# esquem_tico_CPLD.net
KiCad netlist of a schematic drawn in EAGLE
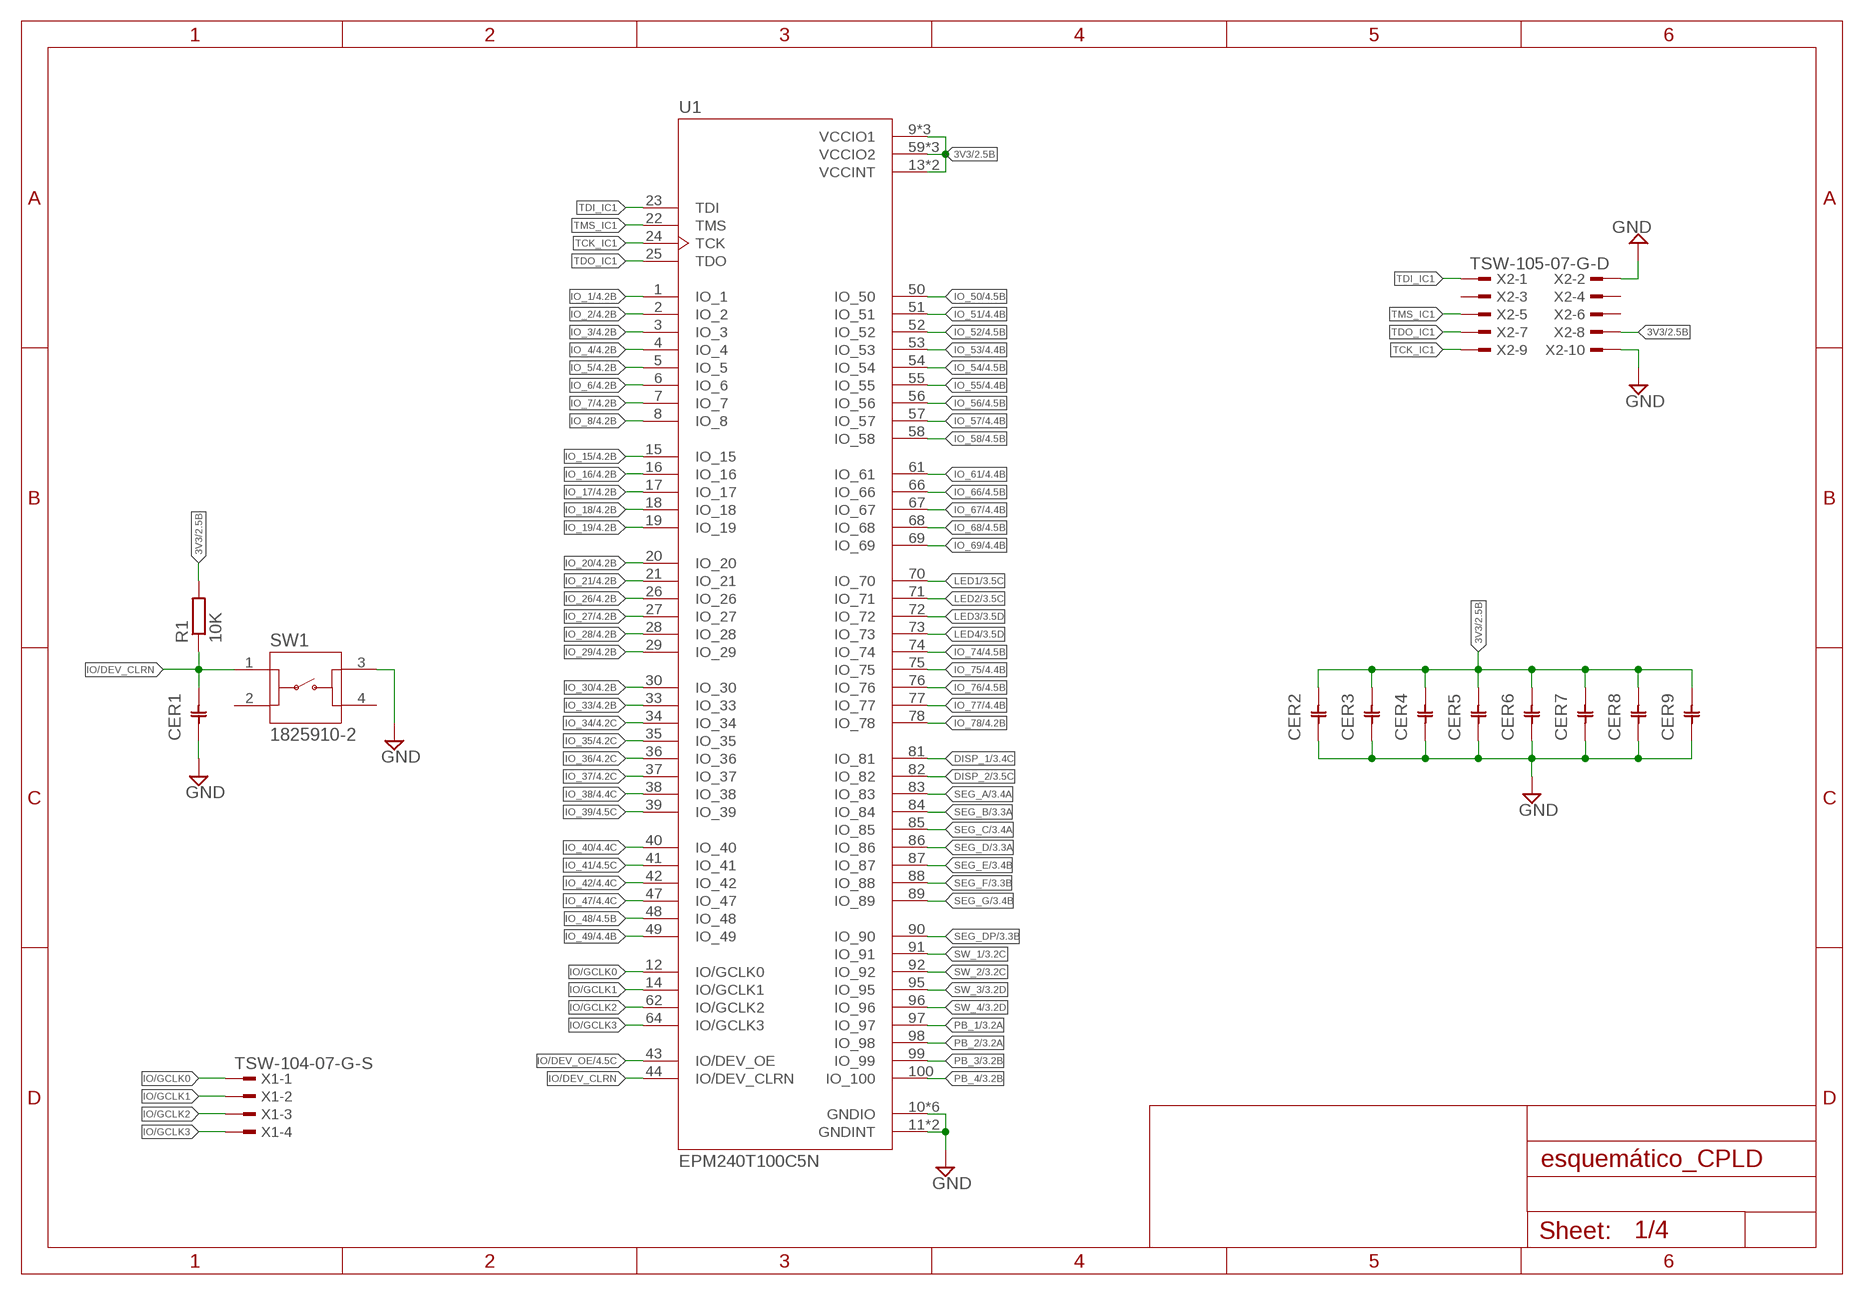
[diagram p0: schematic, sheet 1]
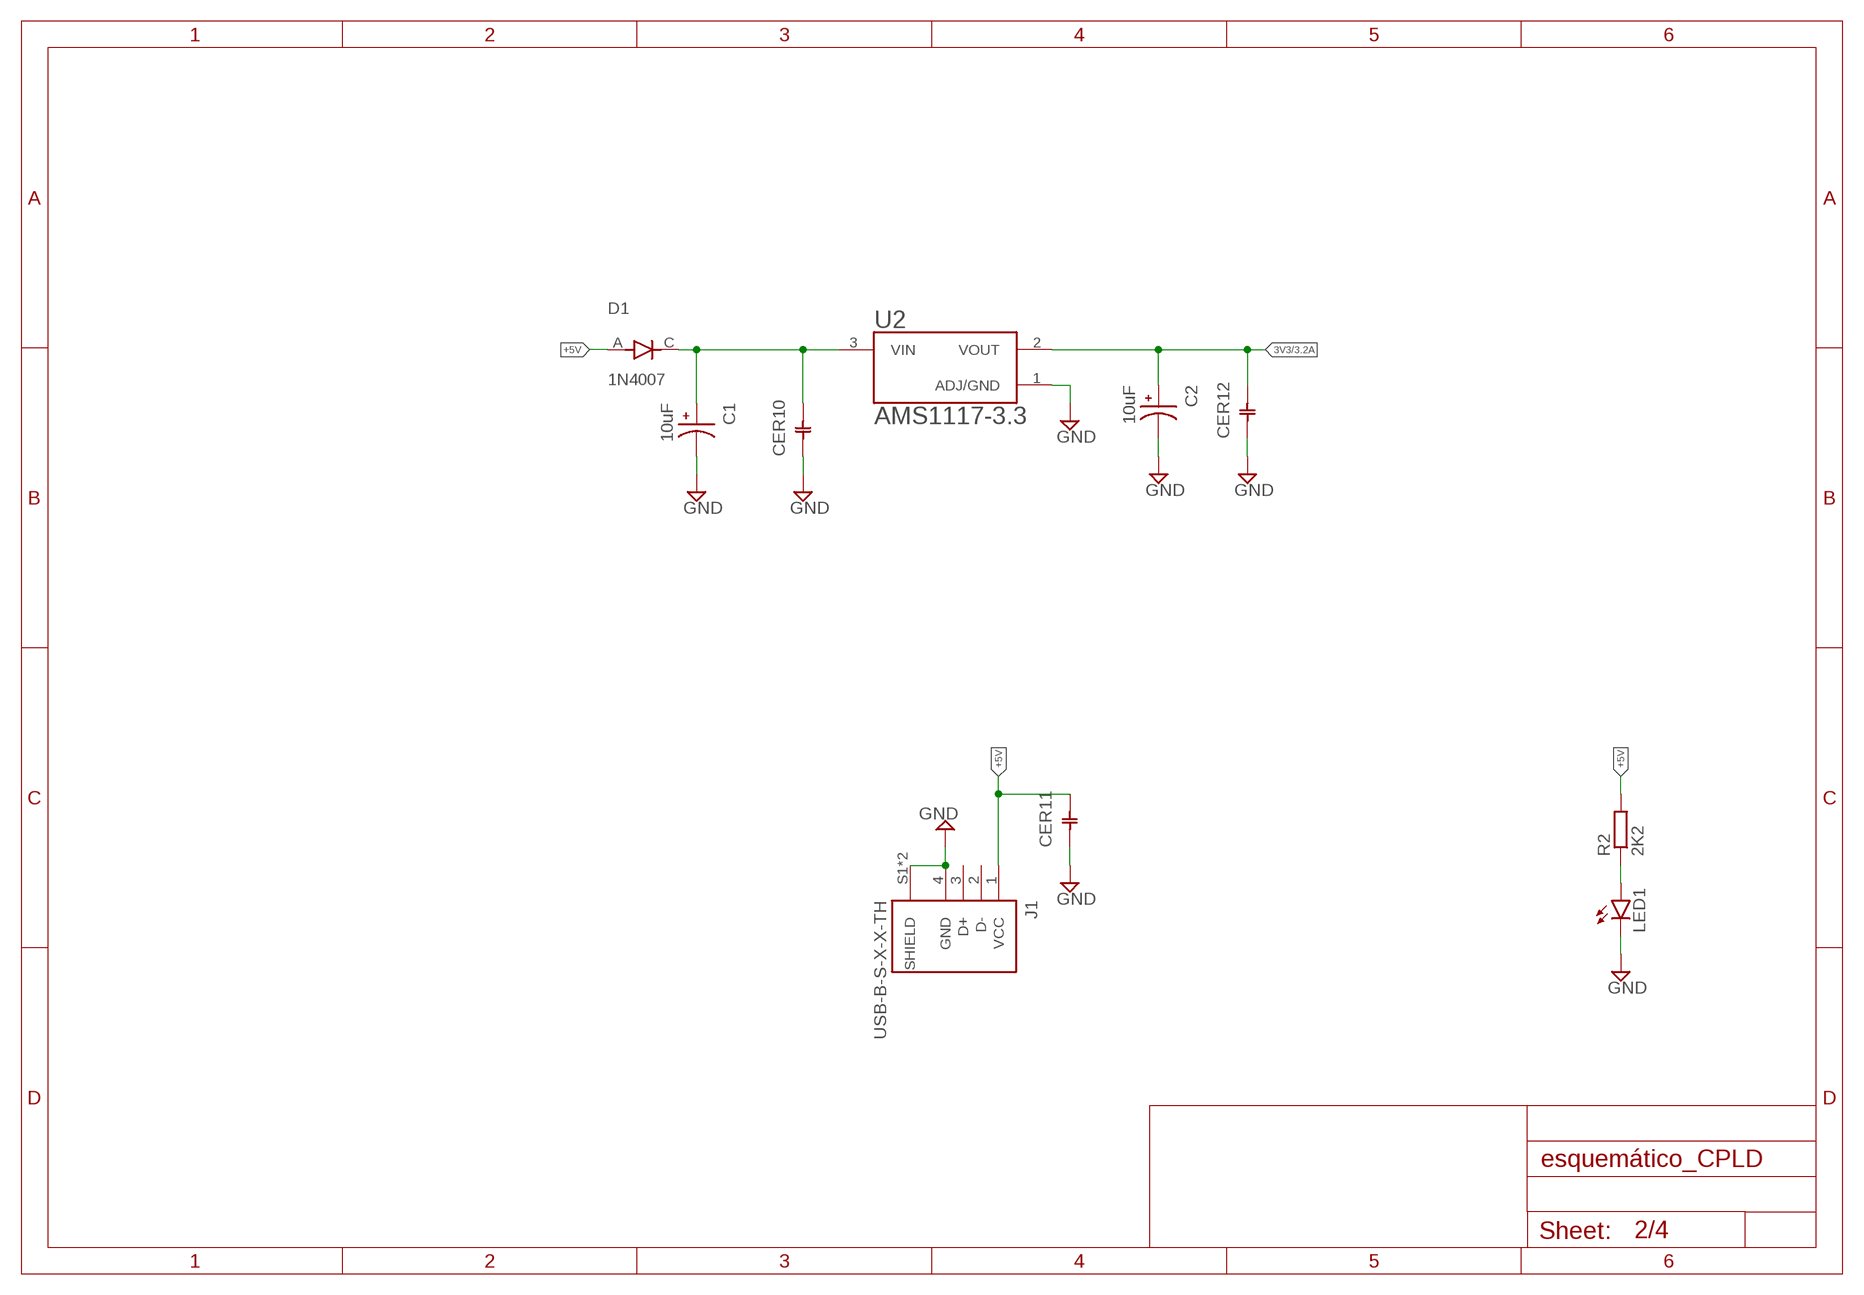
[diagram p1: schematic, sheet 2]
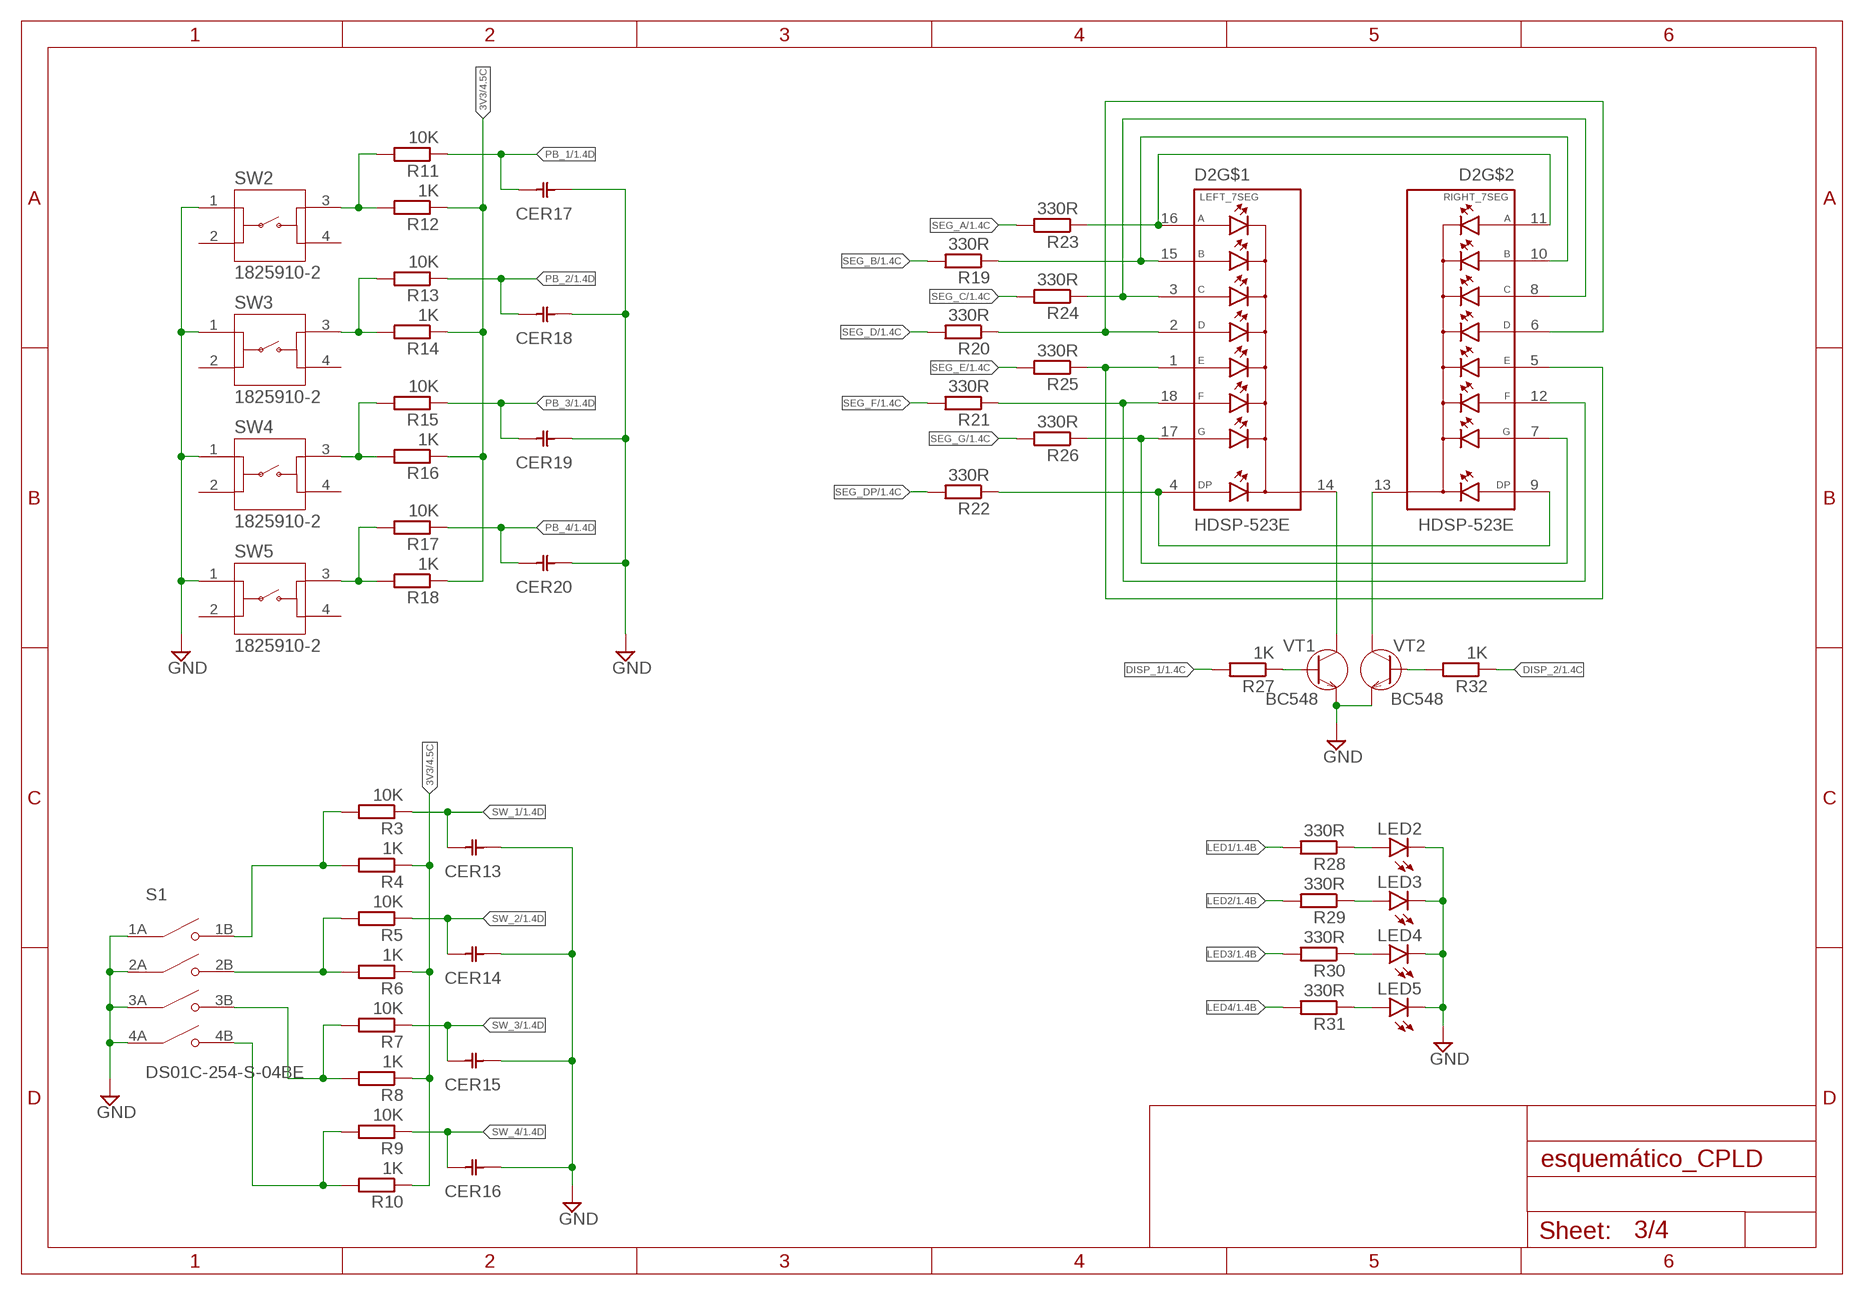
[diagram p2: schematic, sheet 3]
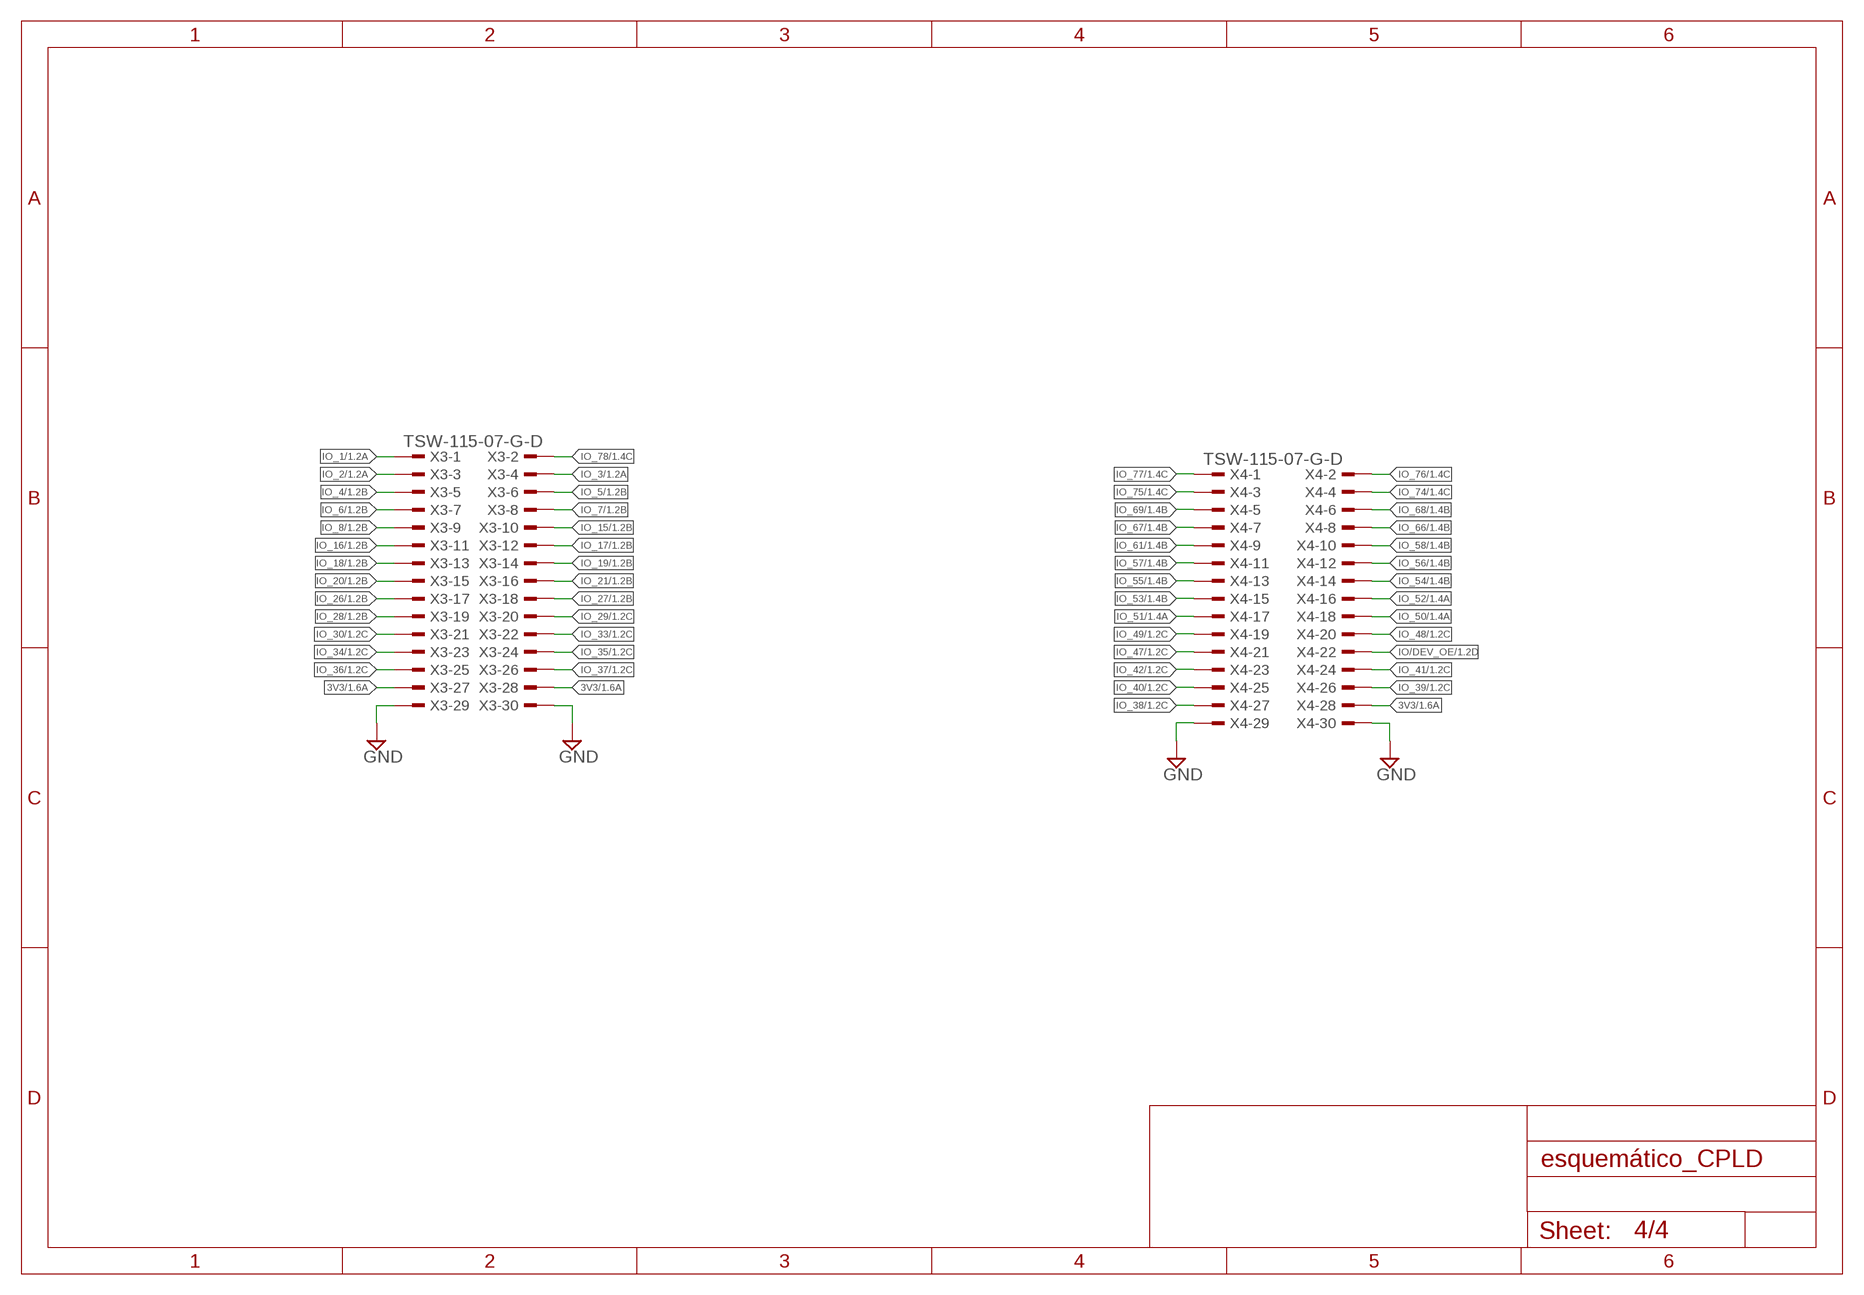
[diagram p3: schematic, sheet 4]

(export (version "E")
  (design (tool "Eeschema 10.0.6"))
  (components
    (comp (ref "CER1")
      (value "100nF")
      (footprint "eagle-import:CERACAPA")
      (libsource (lib "eagle-import") (part "-CERACAP"))
    )
    (comp (ref "CER2")
      (value "100nF")
      (footprint "eagle-import:CERACAPA")
      (libsource (lib "eagle-import") (part "-CERACAP"))
    )
    (comp (ref "CER3")
      (value "100nF")
      (footprint "eagle-import:CERACAPA")
      (libsource (lib "eagle-import") (part "-CERACAP"))
    )
    (comp (ref "CER4")
      (value "100nF")
      (footprint "eagle-import:CERACAPA")
      (libsource (lib "eagle-import") (part "-CERACAP"))
    )
    (comp (ref "CER5")
      (value "100nF")
      (footprint "eagle-import:CERACAPA")
      (libsource (lib "eagle-import") (part "-CERACAP"))
    )
    (comp (ref "CER6")
      (value "100nF")
      (footprint "eagle-import:CERACAPA")
      (libsource (lib "eagle-import") (part "-CERACAP"))
    )
    (comp (ref "CER7")
      (value "100nF")
      (footprint "eagle-import:CERACAPA")
      (libsource (lib "eagle-import") (part "-CERACAP"))
    )
    (comp (ref "CER8")
      (value "100nF")
      (footprint "eagle-import:CERACAPA")
      (libsource (lib "eagle-import") (part "-CERACAP"))
    )
    (comp (ref "CER9")
      (value "100nF")
      (footprint "eagle-import:CERACAPA")
      (libsource (lib "eagle-import") (part "-CERACAP"))
    )
    (comp (ref "R1")
      (value "10K")
      (footprint "eagle-import:0204_7")
      (libsource (lib "eagle-import") (part "R-EU_0204/7"))
    )
    (comp (ref "SW1")
      (value "1825910-2")
      (footprint "eagle-import:TE_1825910-2")
      (fields (field (name "MF") "TE Connectivity"))
      (libsource (lib "eagle-import") (part "1825910-2"))
    )
    (comp (ref "U1")
      (value "EPM240T100C5N")
      (footprint "eagle-import:QFP50P1600X1600X120-100N")
      (fields (field (name "MF") "Intel"))
      (libsource (lib "eagle-import") (part "EPM240T100C5N"))
    )
    (comp (ref "X1")
      (value "TSW-104-07-G-S")
      (footprint "eagle-import:TSW-104-XX-G-S")
      (fields (field (name "MF") "Samtec Inc."))
      (libsource (lib "eagle-import") (part "TSW-104--G-S07"))
    )
    (comp (ref "X2")
      (value "TSW-105-07-G-D")
      (footprint "eagle-import:TSW-105-XX-G-D")
      (fields (field (name "MF") "Samtec Inc."))
      (libsource (lib "eagle-import") (part "TSW-105--G-D07"))
    )
    (comp (ref "C1")
      (value "10uF")
      (footprint "eagle-import:CAPPRD150W45D400H700")
      (fields (field (name "MF") "Panasonic") (field (name "MP") "EEAGA1E100"))
      (libsource (lib "eagle-import") (part "EEAGA1E100"))
    )
    (comp (ref "C2")
      (value "10uF")
      (footprint "eagle-import:CAPPRD150W45D400H700")
      (fields (field (name "MF") "Panasonic") (field (name "MP") "EEAGA1E100"))
      (libsource (lib "eagle-import") (part "EEAGA1E100"))
    )
    (comp (ref "CER10")
      (value "100nF")
      (footprint "eagle-import:CERACAPA")
      (libsource (lib "eagle-import") (part "-CERACAP"))
    )
    (comp (ref "CER11")
      (value "100nF")
      (footprint "eagle-import:CERACAPA")
      (libsource (lib "eagle-import") (part "-CERACAP"))
    )
    (comp (ref "CER12")
      (value "100nF")
      (footprint "eagle-import:CERACAPA")
      (libsource (lib "eagle-import") (part "-CERACAP"))
    )
    (comp (ref "D1")
      (value "1N4007")
      (footprint "eagle-import:DIOAD1060W80L520D270")
      (fields (field (name "MF") "Multicomp") (field (name "MP") "1N4007."))
      (libsource (lib "eagle-import") (part "1N4007"))
    )
    (comp (ref "J1")
      (value "USB-B-S-X-X-TH")
      (footprint "eagle-import:SAMTEC_USB-B-S-X-X-TH")
      (fields (field (name "MF") "Samtec") (field (name "MP") "USB-B-S-F-B-TH-TR"))
      (libsource (lib "eagle-import") (part "USB-B-S-X-X-TH"))
    )
    (comp (ref "LED1")
      (value "LED5MM")
      (footprint "eagle-import:LED5MM")
      (libsource (lib "eagle-import") (part "LED5MM"))
    )
    (comp (ref "R2")
      (value "2K2")
      (footprint "eagle-import:0204_7")
      (libsource (lib "eagle-import") (part "R-EU_0204/7"))
    )
    (comp (ref "U2")
      (value "AMS1117-3.3")
      (footprint "eagle-import:SOT229P700X180-4N")
      (fields (field (name "MF") "Advanced Monolithic Systems"))
      (libsource (lib "eagle-import") (part "AMS1117-3.3"))
    )
    (comp (ref "X3")
      (value "TSW-115-07-G-D")
      (footprint "eagle-import:TSW-115-XX-G-D")
      (fields (field (name "MF") "Samtec Inc."))
      (libsource (lib "eagle-import") (part "TSW-115--G-D07"))
    )
    (comp (ref "X4")
      (value "TSW-115-07-G-D")
      (footprint "eagle-import:TSW-115-XX-G-D")
      (fields (field (name "MF") "Samtec Inc."))
      (libsource (lib "eagle-import") (part "TSW-115--G-D07"))
    )
    (comp (ref "CER13")
      (value "100nF")
      (footprint "eagle-import:CERACAPA")
      (libsource (lib "eagle-import") (part "-CERACAP"))
    )
    (comp (ref "CER14")
      (value "100nF")
      (footprint "eagle-import:CERACAPA")
      (libsource (lib "eagle-import") (part "-CERACAP"))
    )
    (comp (ref "CER15")
      (value "100nF")
      (footprint "eagle-import:CERACAPA")
      (libsource (lib "eagle-import") (part "-CERACAP"))
    )
    (comp (ref "CER16")
      (value "100nF")
      (footprint "eagle-import:CERACAPA")
      (libsource (lib "eagle-import") (part "-CERACAP"))
    )
    (comp (ref "CER17")
      (value "100nF")
      (footprint "eagle-import:CERACAPA")
      (libsource (lib "eagle-import") (part "-CERACAP"))
    )
    (comp (ref "CER18")
      (value "100nF")
      (footprint "eagle-import:CERACAPA")
      (libsource (lib "eagle-import") (part "-CERACAP"))
    )
    (comp (ref "CER19")
      (value "100nF")
      (footprint "eagle-import:CERACAPA")
      (libsource (lib "eagle-import") (part "-CERACAP"))
    )
    (comp (ref "CER20")
      (value "100nF")
      (footprint "eagle-import:CERACAPA")
      (libsource (lib "eagle-import") (part "-CERACAP"))
    )
    (comp (ref "D2")
      (value "HDSP-523E")
      (footprint "eagle-import:LED_HDSP-523E")
      (fields (field (name "MF") "Broadcom"))
      (libsource (lib "eagle-import") (part "HDSP-523E"))
    )
    (comp (ref "LED2")
      (value "LED5MM")
      (footprint "eagle-import:LED5MM")
      (libsource (lib "eagle-import") (part "LED5MM"))
    )
    (comp (ref "LED3")
      (value "LED5MM")
      (footprint "eagle-import:LED5MM")
      (libsource (lib "eagle-import") (part "LED5MM"))
    )
    (comp (ref "LED4")
      (value "LED5MM")
      (footprint "eagle-import:LED5MM")
      (libsource (lib "eagle-import") (part "LED5MM"))
    )
    (comp (ref "LED5")
      (value "LED5MM")
      (footprint "eagle-import:LED5MM")
      (libsource (lib "eagle-import") (part "LED5MM"))
    )
    (comp (ref "R3")
      (value "10K")
      (footprint "eagle-import:0204_7")
      (libsource (lib "eagle-import") (part "R-EU_0204/7"))
    )
    (comp (ref "R4")
      (value "1K")
      (footprint "eagle-import:0204_7")
      (libsource (lib "eagle-import") (part "R-EU_0204/7"))
    )
    (comp (ref "R5")
      (value "10K")
      (footprint "eagle-import:0204_7")
      (libsource (lib "eagle-import") (part "R-EU_0204/7"))
    )
    (comp (ref "R6")
      (value "1K")
      (footprint "eagle-import:0204_7")
      (libsource (lib "eagle-import") (part "R-EU_0204/7"))
    )
    (comp (ref "R7")
      (value "10K")
      (footprint "eagle-import:0204_7")
      (libsource (lib "eagle-import") (part "R-EU_0204/7"))
    )
    (comp (ref "R8")
      (value "1K")
      (footprint "eagle-import:0204_7")
      (libsource (lib "eagle-import") (part "R-EU_0204/7"))
    )
    (comp (ref "R9")
      (value "10K")
      (footprint "eagle-import:0204_7")
      (libsource (lib "eagle-import") (part "R-EU_0204/7"))
    )
    (comp (ref "R10")
      (value "1K")
      (footprint "eagle-import:0204_7")
      (libsource (lib "eagle-import") (part "R-EU_0204/7"))
    )
    (comp (ref "R11")
      (value "10K")
      (footprint "eagle-import:0204_7")
      (libsource (lib "eagle-import") (part "R-EU_0204/7"))
    )
    (comp (ref "R12")
      (value "1K")
      (footprint "eagle-import:0204_7")
      (libsource (lib "eagle-import") (part "R-EU_0204/7"))
    )
    (comp (ref "R13")
      (value "10K")
      (footprint "eagle-import:0204_7")
      (libsource (lib "eagle-import") (part "R-EU_0204/7"))
    )
    (comp (ref "R14")
      (value "1K")
      (footprint "eagle-import:0204_7")
      (libsource (lib "eagle-import") (part "R-EU_0204/7"))
    )
    (comp (ref "R15")
      (value "10K")
      (footprint "eagle-import:0204_7")
      (libsource (lib "eagle-import") (part "R-EU_0204/7"))
    )
    (comp (ref "R16")
      (value "1K")
      (footprint "eagle-import:0204_7")
      (libsource (lib "eagle-import") (part "R-EU_0204/7"))
    )
    (comp (ref "R17")
      (value "10K")
      (footprint "eagle-import:0204_7")
      (libsource (lib "eagle-import") (part "R-EU_0204/7"))
    )
    (comp (ref "R18")
      (value "1K")
      (footprint "eagle-import:0204_7")
      (libsource (lib "eagle-import") (part "R-EU_0204/7"))
    )
    (comp (ref "R19")
      (value "330R")
      (footprint "eagle-import:0204_7")
      (libsource (lib "eagle-import") (part "R-EU_0204/7"))
    )
    (comp (ref "R20")
      (value "330R")
      (footprint "eagle-import:0204_7")
      (libsource (lib "eagle-import") (part "R-EU_0204/7"))
    )
    (comp (ref "R21")
      (value "330R")
      (footprint "eagle-import:0204_7")
      (libsource (lib "eagle-import") (part "R-EU_0204/7"))
    )
    (comp (ref "R22")
      (value "330R")
      (footprint "eagle-import:0204_7")
      (libsource (lib "eagle-import") (part "R-EU_0204/7"))
    )
    (comp (ref "R23")
      (value "330R")
      (footprint "eagle-import:0204_7")
      (libsource (lib "eagle-import") (part "R-EU_0204/7"))
    )
    (comp (ref "R24")
      (value "330R")
      (footprint "eagle-import:0204_7")
      (libsource (lib "eagle-import") (part "R-EU_0204/7"))
    )
    (comp (ref "R25")
      (value "330R")
      (footprint "eagle-import:0204_7")
      (libsource (lib "eagle-import") (part "R-EU_0204/7"))
    )
    (comp (ref "R26")
      (value "330R")
      (footprint "eagle-import:0204_7")
      (libsource (lib "eagle-import") (part "R-EU_0204/7"))
    )
    (comp (ref "R27")
      (value "1K")
      (footprint "eagle-import:0204_7")
      (libsource (lib "eagle-import") (part "R-EU_0204/7"))
    )
    (comp (ref "R28")
      (value "330R")
      (footprint "eagle-import:0204_7")
      (libsource (lib "eagle-import") (part "R-EU_0204/7"))
    )
    (comp (ref "R29")
      (value "330R")
      (footprint "eagle-import:0204_7")
      (libsource (lib "eagle-import") (part "R-EU_0204/7"))
    )
    (comp (ref "R30")
      (value "330R")
      (footprint "eagle-import:0204_7")
      (libsource (lib "eagle-import") (part "R-EU_0204/7"))
    )
    (comp (ref "R31")
      (value "330R")
      (footprint "eagle-import:0204_7")
      (libsource (lib "eagle-import") (part "R-EU_0204/7"))
    )
    (comp (ref "R32")
      (value "1K")
      (footprint "eagle-import:0204_7")
      (libsource (lib "eagle-import") (part "R-EU_0204/7"))
    )
    (comp (ref "S1")
      (value "DS01C-254-S-04BE")
      (footprint "eagle-import:SW_DS01C-254-S-04BE")
      (fields (field (name "MF") "CUI Devices"))
      (libsource (lib "eagle-import") (part "DS01C-254-S-04BE"))
    )
    (comp (ref "SW2")
      (value "1825910-2")
      (footprint "eagle-import:TE_1825910-2")
      (fields (field (name "MF") "TE Connectivity"))
      (libsource (lib "eagle-import") (part "1825910-2"))
    )
    (comp (ref "SW3")
      (value "1825910-2")
      (footprint "eagle-import:TE_1825910-2")
      (fields (field (name "MF") "TE Connectivity"))
      (libsource (lib "eagle-import") (part "1825910-2"))
    )
    (comp (ref "SW4")
      (value "1825910-2")
      (footprint "eagle-import:TE_1825910-2")
      (fields (field (name "MF") "TE Connectivity"))
      (libsource (lib "eagle-import") (part "1825910-2"))
    )
    (comp (ref "SW5")
      (value "1825910-2")
      (footprint "eagle-import:TE_1825910-2")
      (fields (field (name "MF") "TE Connectivity"))
      (libsource (lib "eagle-import") (part "1825910-2"))
    )
    (comp (ref "VT1")
      (value "BC548")
      (footprint "eagle-import:TO92")
      (fields (field (name "MF") "ON"))
      (libsource (lib "eagle-import") (part "BC548"))
    )
    (comp (ref "VT2")
      (value "BC548")
      (footprint "eagle-import:TO92")
      (fields (field (name "MF") "ON"))
      (libsource (lib "eagle-import") (part "BC548"))
    )
  )
  (nets
    (net (code "1") (name "+5V") (class "Default")
      (node (ref "CER11") (pin "P$2") (pinfunction "P$2_P$2") (pintype "passive"))
      (node (ref "D1") (pin "A") (pinfunction "A_A") (pintype "passive"))
      (node (ref "J1") (pin "1") (pinfunction "VCC_1") (pintype "power_in"))
      (node (ref "R2") (pin "2") (pinfunction "2_2") (pintype "passive"))
    )
    (net (code "2") (name "3V3") (class "Default")
      (node (ref "C2") (pin "P") (pinfunction "P_P") (pintype "passive"))
      (node (ref "CER12") (pin "P$2") (pinfunction "P$2_P$2") (pintype "passive"))
      (node (ref "CER2") (pin "P$2") (pinfunction "P$2_P$2") (pintype "passive"))
      (node (ref "CER3") (pin "P$2") (pinfunction "P$2_P$2") (pintype "passive"))
      (node (ref "CER4") (pin "P$2") (pinfunction "P$2_P$2") (pintype "passive"))
      (node (ref "CER5") (pin "P$2") (pinfunction "P$2_P$2") (pintype "passive"))
      (node (ref "CER6") (pin "P$2") (pinfunction "P$2_P$2") (pintype "passive"))
      (node (ref "CER7") (pin "P$2") (pinfunction "P$2_P$2") (pintype "passive"))
      (node (ref "CER8") (pin "P$2") (pinfunction "P$2_P$2") (pintype "passive"))
      (node (ref "CER9") (pin "P$2") (pinfunction "P$2_P$2") (pintype "passive"))
      (node (ref "R1") (pin "2") (pinfunction "2_2") (pintype "passive"))
      (node (ref "R10") (pin "1") (pinfunction "1_1") (pintype "passive"))
      (node (ref "R12") (pin "1") (pinfunction "1_1") (pintype "passive"))
      (node (ref "R14") (pin "1") (pinfunction "1_1") (pintype "passive"))
      (node (ref "R16") (pin "1") (pinfunction "1_1") (pintype "passive"))
      (node (ref "R18") (pin "1") (pinfunction "1_1") (pintype "passive"))
      (node (ref "R4") (pin "1") (pinfunction "1_1") (pintype "passive"))
      (node (ref "R6") (pin "1") (pinfunction "1_1") (pintype "passive"))
      (node (ref "R8") (pin "1") (pinfunction "1_1") (pintype "passive"))
      (node (ref "U1") (pin "13") (pinfunction "VCCINT_13") (pintype "power_in"))
      (node (ref "U1") (pin "31") (pinfunction "VCCIO1_31") (pintype "power_in"))
      (node (ref "U1") (pin "45") (pinfunction "VCCIO1_45") (pintype "power_in"))
      (node (ref "U1") (pin "59") (pinfunction "VCCIO2_59") (pintype "power_in"))
      (node (ref "U1") (pin "63") (pinfunction "VCCINT_63") (pintype "power_in"))
      (node (ref "U1") (pin "80") (pinfunction "VCCIO2_80") (pintype "power_in"))
      (node (ref "U1") (pin "9") (pinfunction "VCCIO1_9") (pintype "power_in"))
      (node (ref "U1") (pin "94") (pinfunction "VCCIO2_94") (pintype "power_in"))
      (node (ref "U2") (pin "2") (pinfunction "VOUT_2") (pintype "output"))
      (node (ref "X2") (pin "8") (pinfunction "1_8") (pintype "passive"))
      (node (ref "X3") (pin "27") (pinfunction "1_27") (pintype "passive"))
      (node (ref "X3") (pin "28") (pinfunction "1_28") (pintype "passive"))
      (node (ref "X4") (pin "28") (pinfunction "1_28") (pintype "passive"))
    )
    (net (code "3") (name "DISP_1") (class "Default")
      (node (ref "R27") (pin "2") (pinfunction "2_2") (pintype "passive"))
      (node (ref "U1") (pin "81") (pinfunction "IO_81_81") (pintype "bidirectional"))
    )
    (net (code "4") (name "DISP_2") (class "Default")
      (node (ref "R32") (pin "1") (pinfunction "1_1") (pintype "passive"))
      (node (ref "U1") (pin "82") (pinfunction "IO_82_82") (pintype "bidirectional"))
    )
    (net (code "5") (name "GND") (class "Default")
      (node (ref "C1") (pin "N") (pinfunction "N_N") (pintype "passive"))
      (node (ref "C2") (pin "N") (pinfunction "N_N") (pintype "passive"))
      (node (ref "CER1") (pin "P$1") (pinfunction "P$1_P$1") (pintype "passive"))
      (node (ref "CER10") (pin "P$1") (pinfunction "P$1_P$1") (pintype "passive"))
      (node (ref "CER11") (pin "P$1") (pinfunction "P$1_P$1") (pintype "passive"))
      (node (ref "CER12") (pin "P$1") (pinfunction "P$1_P$1") (pintype "passive"))
      (node (ref "CER13") (pin "P$1") (pinfunction "P$1_P$1") (pintype "passive"))
      (node (ref "CER14") (pin "P$1") (pinfunction "P$1_P$1") (pintype "passive"))
      (node (ref "CER15") (pin "P$1") (pinfunction "P$1_P$1") (pintype "passive"))
      (node (ref "CER16") (pin "P$1") (pinfunction "P$1_P$1") (pintype "passive"))
      (node (ref "CER17") (pin "P$1") (pinfunction "P$1_P$1") (pintype "passive"))
      (node (ref "CER18") (pin "P$1") (pinfunction "P$1_P$1") (pintype "passive"))
      (node (ref "CER19") (pin "P$1") (pinfunction "P$1_P$1") (pintype "passive"))
      (node (ref "CER2") (pin "P$1") (pinfunction "P$1_P$1") (pintype "passive"))
      (node (ref "CER20") (pin "P$1") (pinfunction "P$1_P$1") (pintype "passive"))
      (node (ref "CER3") (pin "P$1") (pinfunction "P$1_P$1") (pintype "passive"))
      (node (ref "CER4") (pin "P$1") (pinfunction "P$1_P$1") (pintype "passive"))
      (node (ref "CER5") (pin "P$1") (pinfunction "P$1_P$1") (pintype "passive"))
      (node (ref "CER6") (pin "P$1") (pinfunction "P$1_P$1") (pintype "passive"))
      (node (ref "CER7") (pin "P$1") (pinfunction "P$1_P$1") (pintype "passive"))
      (node (ref "CER8") (pin "P$1") (pinfunction "P$1_P$1") (pintype "passive"))
      (node (ref "CER9") (pin "P$1") (pinfunction "P$1_P$1") (pintype "passive"))
      (node (ref "J1") (pin "4") (pinfunction "GND_4") (pintype "power_in"))
      (node (ref "J1") (pin "S1") (pinfunction "SHIELD_S1") (pintype "passive"))
      (node (ref "J1") (pin "S2") (pinfunction "SHIELD_S2") (pintype "passive"))
      (node (ref "LED1") (pin "K") (pinfunction "C_K") (pintype "passive"))
      (node (ref "LED2") (pin "K") (pinfunction "C_K") (pintype "passive"))
      (node (ref "LED3") (pin "K") (pinfunction "C_K") (pintype "passive"))
      (node (ref "LED4") (pin "K") (pinfunction "C_K") (pintype "passive"))
      (node (ref "LED5") (pin "K") (pinfunction "C_K") (pintype "passive"))
      (node (ref "S1") (pin "1A") (pinfunction "COM1_1A") (pintype "passive"))
      (node (ref "S1") (pin "2A") (pinfunction "COM2_2A") (pintype "passive"))
      (node (ref "S1") (pin "3A") (pinfunction "COM3_3A") (pintype "passive"))
      (node (ref "S1") (pin "4A") (pinfunction "COM4_4A") (pintype "passive"))
      (node (ref "SW1") (pin "3") (pinfunction "3_3") (pintype "passive"))
      (node (ref "SW2") (pin "1") (pinfunction "1_1") (pintype "passive"))
      (node (ref "SW3") (pin "1") (pinfunction "1_1") (pintype "passive"))
      (node (ref "SW4") (pin "1") (pinfunction "1_1") (pintype "passive"))
      (node (ref "SW5") (pin "1") (pinfunction "1_1") (pintype "passive"))
      (node (ref "U1") (pin "10") (pinfunction "GNDIO_10") (pintype "power_in"))
      (node (ref "U1") (pin "11") (pinfunction "GNDINT_11") (pintype "power_in"))
      (node (ref "U1") (pin "32") (pinfunction "GNDIO_32") (pintype "power_in"))
      (node (ref "U1") (pin "46") (pinfunction "GNDIO_46") (pintype "power_in"))
      (node (ref "U1") (pin "60") (pinfunction "GNDIO_60") (pintype "power_in"))
      (node (ref "U1") (pin "65") (pinfunction "GNDINT_65") (pintype "power_in"))
      (node (ref "U1") (pin "79") (pinfunction "GNDIO_79") (pintype "power_in"))
      (node (ref "U1") (pin "93") (pinfunction "GNDIO_93") (pintype "power_in"))
      (node (ref "U2") (pin "1") (pinfunction "ADJ/GND_1") (pintype "power_in"))
      (node (ref "VT1") (pin "E") (pinfunction "E_E") (pintype "passive"))
      (node (ref "VT2") (pin "E") (pinfunction "E_E") (pintype "passive"))
      (node (ref "X2") (pin "10") (pinfunction "1_10") (pintype "passive"))
      (node (ref "X2") (pin "2") (pinfunction "1_2") (pintype "passive"))
      (node (ref "X3") (pin "29") (pinfunction "1_29") (pintype "passive"))
      (node (ref "X3") (pin "30") (pinfunction "1_30") (pintype "passive"))
      (node (ref "X4") (pin "29") (pinfunction "1_29") (pintype "passive"))
      (node (ref "X4") (pin "30") (pinfunction "1_30") (pintype "passive"))
    )
    (net (code "6") (name "IO_1") (class "Default")
      (node (ref "U1") (pin "1") (pinfunction "IO_1_1") (pintype "bidirectional"))
      (node (ref "X3") (pin "1") (pinfunction "1_1") (pintype "passive"))
    )
    (net (code "7") (name "IO_2") (class "Default")
      (node (ref "U1") (pin "2") (pinfunction "IO_2_2") (pintype "bidirectional"))
      (node (ref "X3") (pin "3") (pinfunction "1_3") (pintype "passive"))
    )
    (net (code "8") (name "IO_3") (class "Default")
      (node (ref "U1") (pin "3") (pinfunction "IO_3_3") (pintype "bidirectional"))
      (node (ref "X3") (pin "4") (pinfunction "1_4") (pintype "passive"))
    )
    (net (code "9") (name "IO_4") (class "Default")
      (node (ref "U1") (pin "4") (pinfunction "IO_4_4") (pintype "bidirectional"))
      (node (ref "X3") (pin "5") (pinfunction "1_5") (pintype "passive"))
    )
    (net (code "10") (name "IO_5") (class "Default")
      (node (ref "U1") (pin "5") (pinfunction "IO_5_5") (pintype "bidirectional"))
      (node (ref "X3") (pin "6") (pinfunction "1_6") (pintype "passive"))
    )
    (net (code "11") (name "IO_6") (class "Default")
      (node (ref "U1") (pin "6") (pinfunction "IO_6_6") (pintype "bidirectional"))
      (node (ref "X3") (pin "7") (pinfunction "1_7") (pintype "passive"))
    )
    (net (code "12") (name "IO_7") (class "Default")
      (node (ref "U1") (pin "7") (pinfunction "IO_7_7") (pintype "bidirectional"))
      (node (ref "X3") (pin "8") (pinfunction "1_8") (pintype "passive"))
    )
    (net (code "13") (name "IO_8") (class "Default")
      (node (ref "U1") (pin "8") (pinfunction "IO_8_8") (pintype "bidirectional"))
      (node (ref "X3") (pin "9") (pinfunction "1_9") (pintype "passive"))
    )
    (net (code "14") (name "IO_15") (class "Default")
      (node (ref "U1") (pin "15") (pinfunction "IO_15_15") (pintype "bidirectional"))
      (node (ref "X3") (pin "10") (pinfunction "1_10") (pintype "passive"))
    )
    (net (code "15") (name "IO_16") (class "Default")
      (node (ref "U1") (pin "16") (pinfunction "IO_16_16") (pintype "bidirectional"))
      (node (ref "X3") (pin "11") (pinfunction "1_11") (pintype "passive"))
    )
    (net (code "16") (name "IO_17") (class "Default")
      (node (ref "U1") (pin "17") (pinfunction "IO_17_17") (pintype "bidirectional"))
      (node (ref "X3") (pin "12") (pinfunction "1_12") (pintype "passive"))
    )
    (net (code "17") (name "IO_18") (class "Default")
      (node (ref "U1") (pin "18") (pinfunction "IO_18_18") (pintype "bidirectional"))
      (node (ref "X3") (pin "13") (pinfunction "1_13") (pintype "passive"))
    )
    (net (code "18") (name "IO_19") (class "Default")
      (node (ref "U1") (pin "19") (pinfunction "IO_19_19") (pintype "bidirectional"))
      (node (ref "X3") (pin "14") (pinfunction "1_14") (pintype "passive"))
    )
    (net (code "19") (name "IO_20") (class "Default")
      (node (ref "U1") (pin "20") (pinfunction "IO_20_20") (pintype "bidirectional"))
      (node (ref "X3") (pin "15") (pinfunction "1_15") (pintype "passive"))
    )
    (net (code "20") (name "IO_21") (class "Default")
      (node (ref "U1") (pin "21") (pinfunction "IO_21_21") (pintype "bidirectional"))
      (node (ref "X3") (pin "16") (pinfunction "1_16") (pintype "passive"))
    )
    (net (code "21") (name "IO_26") (class "Default")
      (node (ref "U1") (pin "26") (pinfunction "IO_26_26") (pintype "bidirectional"))
      (node (ref "X3") (pin "17") (pinfunction "1_17") (pintype "passive"))
    )
    (net (code "22") (name "IO_27") (class "Default")
      (node (ref "U1") (pin "27") (pinfunction "IO_27_27") (pintype "bidirectional"))
      (node (ref "X3") (pin "18") (pinfunction "1_18") (pintype "passive"))
    )
    (net (code "23") (name "IO_28") (class "Default")
      (node (ref "U1") (pin "28") (pinfunction "IO_28_28") (pintype "bidirectional"))
      (node (ref "X3") (pin "19") (pinfunction "1_19") (pintype "passive"))
    )
    (net (code "24") (name "IO_29") (class "Default")
      (node (ref "U1") (pin "29") (pinfunction "IO_29_29") (pintype "bidirectional"))
      (node (ref "X3") (pin "20") (pinfunction "1_20") (pintype "passive"))
    )
    (net (code "25") (name "IO_30") (class "Default")
      (node (ref "U1") (pin "30") (pinfunction "IO_30_30") (pintype "bidirectional"))
      (node (ref "X3") (pin "21") (pinfunction "1_21") (pintype "passive"))
    )
    (net (code "26") (name "IO_33") (class "Default")
      (node (ref "U1") (pin "33") (pinfunction "IO_33_33") (pintype "bidirectional"))
      (node (ref "X3") (pin "22") (pinfunction "1_22") (pintype "passive"))
    )
    (net (code "27") (name "IO_34") (class "Default")
      (node (ref "U1") (pin "34") (pinfunction "IO_34_34") (pintype "bidirectional"))
      (node (ref "X3") (pin "23") (pinfunction "1_23") (pintype "passive"))
    )
    (net (code "28") (name "IO_35") (class "Default")
      (node (ref "U1") (pin "35") (pinfunction "IO_35_35") (pintype "bidirectional"))
      (node (ref "X3") (pin "24") (pinfunction "1_24") (pintype "passive"))
    )
    (net (code "29") (name "IO_36") (class "Default")
      (node (ref "U1") (pin "36") (pinfunction "IO_36_36") (pintype "bidirectional"))
      (node (ref "X3") (pin "25") (pinfunction "1_25") (pintype "passive"))
    )
    (net (code "30") (name "IO_37") (class "Default")
      (node (ref "U1") (pin "37") (pinfunction "IO_37_37") (pintype "bidirectional"))
      (node (ref "X3") (pin "26") (pinfunction "1_26") (pintype "passive"))
    )
    (net (code "31") (name "IO_38") (class "Default")
      (node (ref "U1") (pin "38") (pinfunction "IO_38_38") (pintype "bidirectional"))
      (node (ref "X4") (pin "27") (pinfunction "1_27") (pintype "passive"))
    )
    (net (code "32") (name "IO_39") (class "Default")
      (node (ref "U1") (pin "39") (pinfunction "IO_39_39") (pintype "bidirectional"))
      (node (ref "X4") (pin "26") (pinfunction "1_26") (pintype "passive"))
    )
    (net (code "33") (name "IO_40") (class "Default")
      (node (ref "U1") (pin "40") (pinfunction "IO_40_40") (pintype "bidirectional"))
      (node (ref "X4") (pin "25") (pinfunction "1_25") (pintype "passive"))
    )
    (net (code "34") (name "IO_41") (class "Default")
      (node (ref "U1") (pin "41") (pinfunction "IO_41_41") (pintype "bidirectional"))
      (node (ref "X4") (pin "24") (pinfunction "1_24") (pintype "passive"))
    )
    (net (code "35") (name "IO_42") (class "Default")
      (node (ref "U1") (pin "42") (pinfunction "IO_42_42") (pintype "bidirectional"))
      (node (ref "X4") (pin "23") (pinfunction "1_23") (pintype "passive"))
    )
    (net (code "36") (name "IO_47") (class "Default")
      (node (ref "U1") (pin "47") (pinfunction "IO_47_47") (pintype "bidirectional"))
      (node (ref "X4") (pin "21") (pinfunction "1_21") (pintype "passive"))
    )
    (net (code "37") (name "IO_48") (class "Default")
      (node (ref "U1") (pin "48") (pinfunction "IO_48_48") (pintype "bidirectional"))
      (node (ref "X4") (pin "20") (pinfunction "1_20") (pintype "passive"))
    )
    (net (code "38") (name "IO_49") (class "Default")
      (node (ref "U1") (pin "49") (pinfunction "IO_49_49") (pintype "bidirectional"))
      (node (ref "X4") (pin "19") (pinfunction "1_19") (pintype "passive"))
    )
    (net (code "39") (name "IO_50") (class "Default")
      (node (ref "U1") (pin "50") (pinfunction "IO_50_50") (pintype "bidirectional"))
      (node (ref "X4") (pin "18") (pinfunction "1_18") (pintype "passive"))
    )
    (net (code "40") (name "IO_51") (class "Default")
      (node (ref "U1") (pin "51") (pinfunction "IO_51_51") (pintype "bidirectional"))
      (node (ref "X4") (pin "17") (pinfunction "1_17") (pintype "passive"))
    )
    (net (code "41") (name "IO_52") (class "Default")
      (node (ref "U1") (pin "52") (pinfunction "IO_52_52") (pintype "bidirectional"))
      (node (ref "X4") (pin "16") (pinfunction "1_16") (pintype "passive"))
    )
    (net (code "42") (name "IO_53") (class "Default")
      (node (ref "U1") (pin "53") (pinfunction "IO_53_53") (pintype "bidirectional"))
      (node (ref "X4") (pin "15") (pinfunction "1_15") (pintype "passive"))
    )
    (net (code "43") (name "IO_54") (class "Default")
      (node (ref "U1") (pin "54") (pinfunction "IO_54_54") (pintype "bidirectional"))
      (node (ref "X4") (pin "14") (pinfunction "1_14") (pintype "passive"))
    )
    (net (code "44") (name "IO_55") (class "Default")
      (node (ref "U1") (pin "55") (pinfunction "IO_55_55") (pintype "bidirectional"))
      (node (ref "X4") (pin "13") (pinfunction "1_13") (pintype "passive"))
    )
    (net (code "45") (name "IO_56") (class "Default")
      (node (ref "U1") (pin "56") (pinfunction "IO_56_56") (pintype "bidirectional"))
      (node (ref "X4") (pin "12") (pinfunction "1_12") (pintype "passive"))
    )
    (net (code "46") (name "IO_57") (class "Default")
      (node (ref "U1") (pin "57") (pinfunction "IO_57_57") (pintype "bidirectional"))
      (node (ref "X4") (pin "11") (pinfunction "1_11") (pintype "passive"))
    )
    (net (code "47") (name "IO_58") (class "Default")
      (node (ref "U1") (pin "58") (pinfunction "IO_58_58") (pintype "bidirectional"))
      (node (ref "X4") (pin "10") (pinfunction "1_10") (pintype "passive"))
    )
    (net (code "48") (name "IO_61") (class "Default")
      (node (ref "U1") (pin "61") (pinfunction "IO_61_61") (pintype "bidirectional"))
      (node (ref "X4") (pin "9") (pinfunction "1_9") (pintype "passive"))
    )
    (net (code "49") (name "IO_66") (class "Default")
      (node (ref "U1") (pin "66") (pinfunction "IO_66_66") (pintype "bidirectional"))
      (node (ref "X4") (pin "8") (pinfunction "1_8") (pintype "passive"))
    )
    (net (code "50") (name "IO_67") (class "Default")
      (node (ref "U1") (pin "67") (pinfunction "IO_67_67") (pintype "bidirectional"))
      (node (ref "X4") (pin "7") (pinfunction "1_7") (pintype "passive"))
    )
    (net (code "51") (name "IO_68") (class "Default")
      (node (ref "U1") (pin "68") (pinfunction "IO_68_68") (pintype "bidirectional"))
      (node (ref "X4") (pin "6") (pinfunction "1_6") (pintype "passive"))
    )
    (net (code "52") (name "IO_69") (class "Default")
      (node (ref "U1") (pin "69") (pinfunction "IO_69_69") (pintype "bidirectional"))
      (node (ref "X4") (pin "5") (pinfunction "1_5") (pintype "passive"))
    )
    (net (code "53") (name "IO_74") (class "Default")
      (node (ref "U1") (pin "74") (pinfunction "IO_74_74") (pintype "bidirectional"))
      (node (ref "X4") (pin "4") (pinfunction "1_4") (pintype "passive"))
    )
    (net (code "54") (name "IO_75") (class "Default")
      (node (ref "U1") (pin "75") (pinfunction "IO_75_75") (pintype "bidirectional"))
      (node (ref "X4") (pin "3") (pinfunction "1_3") (pintype "passive"))
    )
    (net (code "55") (name "IO_76") (class "Default")
      (node (ref "U1") (pin "76") (pinfunction "IO_76_76") (pintype "bidirectional"))
      (node (ref "X4") (pin "2") (pinfunction "1_2") (pintype "passive"))
    )
    (net (code "56") (name "IO_77") (class "Default")
      (node (ref "U1") (pin "77") (pinfunction "IO_77_77") (pintype "bidirectional"))
      (node (ref "X4") (pin "1") (pinfunction "1_1") (pintype "passive"))
    )
    (net (code "57") (name "IO_78") (class "Default")
      (node (ref "U1") (pin "78") (pinfunction "IO_78_78") (pintype "bidirectional"))
      (node (ref "X3") (pin "2") (pinfunction "1_2") (pintype "passive"))
    )
    (net (code "58") (name "IO{slash}DEV_CLRN") (class "Default")
      (node (ref "CER1") (pin "P$2") (pinfunction "P$2_P$2") (pintype "passive"))
      (node (ref "R1") (pin "1") (pinfunction "1_1") (pintype "passive"))
      (node (ref "SW1") (pin "1") (pinfunction "1_1") (pintype "passive"))
      (node (ref "U1") (pin "44") (pinfunction "IO/DEV_CLRN_44") (pintype "bidirectional"))
    )
    (net (code "59") (name "IO{slash}DEV_OE") (class "Default")
      (node (ref "U1") (pin "43") (pinfunction "IO/DEV_OE_43") (pintype "bidirectional"))
      (node (ref "X4") (pin "22") (pinfunction "1_22") (pintype "passive"))
    )
    (net (code "60") (name "IO{slash}GCLK0") (class "Default")
      (node (ref "U1") (pin "12") (pinfunction "IO/GCLK0_12") (pintype "bidirectional"))
      (node (ref "X1") (pin "1") (pinfunction "1_1") (pintype "passive"))
    )
    (net (code "61") (name "IO{slash}GCLK1") (class "Default")
      (node (ref "U1") (pin "14") (pinfunction "IO/GCLK1_14") (pintype "bidirectional"))
      (node (ref "X1") (pin "2") (pinfunction "1_2") (pintype "passive"))
    )
    (net (code "62") (name "IO{slash}GCLK2") (class "Default")
      (node (ref "U1") (pin "62") (pinfunction "IO/GCLK2_62") (pintype "bidirectional"))
      (node (ref "X1") (pin "3") (pinfunction "1_3") (pintype "passive"))
    )
    (net (code "63") (name "IO{slash}GCLK3") (class "Default")
      (node (ref "U1") (pin "64") (pinfunction "IO/GCLK3_64") (pintype "bidirectional"))
      (node (ref "X1") (pin "4") (pinfunction "1_4") (pintype "passive"))
    )
    (net (code "64") (name "LED1") (class "Default")
      (node (ref "R28") (pin "2") (pinfunction "2_2") (pintype "passive"))
      (node (ref "U1") (pin "70") (pinfunction "IO_70_70") (pintype "bidirectional"))
    )
    (net (code "65") (name "LED2") (class "Default")
      (node (ref "R29") (pin "2") (pinfunction "2_2") (pintype "passive"))
      (node (ref "U1") (pin "71") (pinfunction "IO_71_71") (pintype "bidirectional"))
    )
    (net (code "66") (name "LED3") (class "Default")
      (node (ref "R30") (pin "2") (pinfunction "2_2") (pintype "passive"))
      (node (ref "U1") (pin "72") (pinfunction "IO_72_72") (pintype "bidirectional"))
    )
    (net (code "67") (name "LED4") (class "Default")
      (node (ref "R31") (pin "2") (pinfunction "2_2") (pintype "passive"))
      (node (ref "U1") (pin "73") (pinfunction "IO_73_73") (pintype "bidirectional"))
    )
    (net (code "68") (name "Net-(D2A-A_1)") (class "Default")
      (node (ref "D2") (pin "11") (pinfunction "A_2_11") (pintype "passive"))
      (node (ref "D2") (pin "16") (pinfunction "A_1_16") (pintype "passive"))
      (node (ref "R23") (pin "1") (pinfunction "1_1") (pintype "passive"))
    )
    (net (code "69") (name "Net-(D2A-B_1)") (class "Default")
      (node (ref "D2") (pin "10") (pinfunction "B_2_10") (pintype "passive"))
      (node (ref "D2") (pin "15") (pinfunction "B_1_15") (pintype "passive"))
      (node (ref "R19") (pin "1") (pinfunction "1_1") (pintype "passive"))
    )
    (net (code "70") (name "Net-(D2A-COM_1)") (class "Default")
      (node (ref "D2") (pin "14") (pinfunction "COM_1_14") (pintype "passive"))
      (node (ref "VT1") (pin "C") (pinfunction "C_C") (pintype "passive"))
    )
    (net (code "71") (name "Net-(D2A-C_1)") (class "Default")
      (node (ref "D2") (pin "3") (pinfunction "C_1_3") (pintype "passive"))
      (node (ref "D2") (pin "8") (pinfunction "C_2_8") (pintype "passive"))
      (node (ref "R24") (pin "1") (pinfunction "1_1") (pintype "passive"))
    )
    (net (code "72") (name "Net-(D2A-DP_1)") (class "Default")
      (node (ref "D2") (pin "4") (pinfunction "DP_1_4") (pintype "passive"))
      (node (ref "D2") (pin "9") (pinfunction "DP_2_9") (pintype "passive"))
      (node (ref "R22") (pin "1") (pinfunction "1_1") (pintype "passive"))
    )
    (net (code "73") (name "Net-(D2A-D_1)") (class "Default")
      (node (ref "D2") (pin "2") (pinfunction "D_1_2") (pintype "passive"))
      (node (ref "D2") (pin "6") (pinfunction "D_2_6") (pintype "passive"))
      (node (ref "R20") (pin "1") (pinfunction "1_1") (pintype "passive"))
    )
    (net (code "74") (name "Net-(D2A-E_1)") (class "Default")
      (node (ref "D2") (pin "1") (pinfunction "E_1_1") (pintype "passive"))
      (node (ref "D2") (pin "5") (pinfunction "E_2_5") (pintype "passive"))
      (node (ref "R25") (pin "1") (pinfunction "1_1") (pintype "passive"))
    )
    (net (code "75") (name "Net-(D2A-F_1)") (class "Default")
      (node (ref "D2") (pin "12") (pinfunction "F_2_12") (pintype "passive"))
      (node (ref "D2") (pin "18") (pinfunction "F_1_18") (pintype "passive"))
      (node (ref "R21") (pin "1") (pinfunction "1_1") (pintype "passive"))
    )
    (net (code "76") (name "Net-(D2A-G_1)") (class "Default")
      (node (ref "D2") (pin "17") (pinfunction "G_1_17") (pintype "passive"))
      (node (ref "D2") (pin "7") (pinfunction "G_2_7") (pintype "passive"))
      (node (ref "R26") (pin "1") (pinfunction "1_1") (pintype "passive"))
    )
    (net (code "77") (name "Net-(D2B-COM_2)") (class "Default")
      (node (ref "D2") (pin "13") (pinfunction "COM_2_13") (pintype "passive"))
      (node (ref "VT2") (pin "C") (pinfunction "C_C") (pintype "passive"))
    )
    (net (code "78") (name "Net-(LED1-PadA)") (class "Default")
      (node (ref "LED1") (pin "A") (pinfunction "A_A") (pintype "passive"))
      (node (ref "R2") (pin "1") (pinfunction "1_1") (pintype "passive"))
    )
    (net (code "79") (name "Net-(LED2-PadA)") (class "Default")
      (node (ref "LED2") (pin "A") (pinfunction "A_A") (pintype "passive"))
      (node (ref "R28") (pin "1") (pinfunction "1_1") (pintype "passive"))
    )
    (net (code "80") (name "Net-(LED3-PadA)") (class "Default")
      (node (ref "LED3") (pin "A") (pinfunction "A_A") (pintype "passive"))
      (node (ref "R29") (pin "1") (pinfunction "1_1") (pintype "passive"))
    )
    (net (code "81") (name "Net-(LED4-PadA)") (class "Default")
      (node (ref "LED4") (pin "A") (pinfunction "A_A") (pintype "passive"))
      (node (ref "R30") (pin "1") (pinfunction "1_1") (pintype "passive"))
    )
    (net (code "82") (name "Net-(LED5-PadA)") (class "Default")
      (node (ref "LED5") (pin "A") (pinfunction "A_A") (pintype "passive"))
      (node (ref "R31") (pin "1") (pinfunction "1_1") (pintype "passive"))
    )
    (net (code "83") (name "Net-(R11-Pad2)") (class "Default")
      (node (ref "R11") (pin "2") (pinfunction "2_2") (pintype "passive"))
      (node (ref "R12") (pin "2") (pinfunction "2_2") (pintype "passive"))
      (node (ref "SW2") (pin "3") (pinfunction "3_3") (pintype "passive"))
    )
    (net (code "84") (name "Net-(R13-Pad2)") (class "Default")
      (node (ref "R13") (pin "2") (pinfunction "2_2") (pintype "passive"))
      (node (ref "R14") (pin "2") (pinfunction "2_2") (pintype "passive"))
      (node (ref "SW3") (pin "3") (pinfunction "3_3") (pintype "passive"))
    )
    (net (code "85") (name "Net-(R15-Pad2)") (class "Default")
      (node (ref "R15") (pin "2") (pinfunction "2_2") (pintype "passive"))
      (node (ref "R16") (pin "2") (pinfunction "2_2") (pintype "passive"))
      (node (ref "SW4") (pin "3") (pinfunction "3_3") (pintype "passive"))
    )
    (net (code "86") (name "Net-(R17-Pad2)") (class "Default")
      (node (ref "R17") (pin "2") (pinfunction "2_2") (pintype "passive"))
      (node (ref "R18") (pin "2") (pinfunction "2_2") (pintype "passive"))
      (node (ref "SW5") (pin "3") (pinfunction "3_3") (pintype "passive"))
    )
    (net (code "87") (name "Net-(R27-Pad1)") (class "Default")
      (node (ref "R27") (pin "1") (pinfunction "1_1") (pintype "passive"))
      (node (ref "VT1") (pin "B") (pinfunction "B_B") (pintype "passive"))
    )
    (net (code "88") (name "Net-(R32-Pad2)") (class "Default")
      (node (ref "R32") (pin "2") (pinfunction "2_2") (pintype "passive"))
      (node (ref "VT2") (pin "B") (pinfunction "B_B") (pintype "passive"))
    )
    (net (code "89") (name "Net-(S1-NO1)") (class "Default")
      (node (ref "R3") (pin "2") (pinfunction "2_2") (pintype "passive"))
      (node (ref "R4") (pin "2") (pinfunction "2_2") (pintype "passive"))
      (node (ref "S1") (pin "1B") (pinfunction "NO1_1B") (pintype "passive"))
    )
    (net (code "90") (name "Net-(S1-NO2)") (class "Default")
      (node (ref "R5") (pin "2") (pinfunction "2_2") (pintype "passive"))
      (node (ref "R6") (pin "2") (pinfunction "2_2") (pintype "passive"))
      (node (ref "S1") (pin "2B") (pinfunction "NO2_2B") (pintype "passive"))
    )
    (net (code "91") (name "Net-(S1-NO3)") (class "Default")
      (node (ref "R7") (pin "2") (pinfunction "2_2") (pintype "passive"))
      (node (ref "R8") (pin "2") (pinfunction "2_2") (pintype "passive"))
      (node (ref "S1") (pin "3B") (pinfunction "NO3_3B") (pintype "passive"))
    )
    (net (code "92") (name "Net-(S1-NO4)") (class "Default")
      (node (ref "R10") (pin "2") (pinfunction "2_2") (pintype "passive"))
      (node (ref "R9") (pin "2") (pinfunction "2_2") (pintype "passive"))
      (node (ref "S1") (pin "4B") (pinfunction "NO4_4B") (pintype "passive"))
    )
    (net (code "93") (name "Net-(U2-VIN)") (class "Default")
      (node (ref "C1") (pin "P") (pinfunction "P_P") (pintype "passive"))
      (node (ref "CER10") (pin "P$2") (pinfunction "P$2_P$2") (pintype "passive"))
      (node (ref "D1") (pin "C") (pinfunction "C_C") (pintype "passive"))
      (node (ref "U2") (pin "3") (pinfunction "VIN_3") (pintype "input"))
    )
    (net (code "94") (name "PB_1") (class "Default")
      (node (ref "CER17") (pin "P$2") (pinfunction "P$2_P$2") (pintype "passive"))
      (node (ref "R11") (pin "1") (pinfunction "1_1") (pintype "passive"))
      (node (ref "U1") (pin "97") (pinfunction "IO_97_97") (pintype "bidirectional"))
    )
    (net (code "95") (name "PB_2") (class "Default")
      (node (ref "CER18") (pin "P$2") (pinfunction "P$2_P$2") (pintype "passive"))
      (node (ref "R13") (pin "1") (pinfunction "1_1") (pintype "passive"))
      (node (ref "U1") (pin "98") (pinfunction "IO_98_98") (pintype "bidirectional"))
    )
    (net (code "96") (name "PB_3") (class "Default")
      (node (ref "CER19") (pin "P$2") (pinfunction "P$2_P$2") (pintype "passive"))
      (node (ref "R15") (pin "1") (pinfunction "1_1") (pintype "passive"))
      (node (ref "U1") (pin "99") (pinfunction "IO_99_99") (pintype "bidirectional"))
    )
    (net (code "97") (name "PB_4") (class "Default")
      (node (ref "CER20") (pin "P$2") (pinfunction "P$2_P$2") (pintype "passive"))
      (node (ref "R17") (pin "1") (pinfunction "1_1") (pintype "passive"))
      (node (ref "U1") (pin "100") (pinfunction "IO_100_100") (pintype "bidirectional"))
    )
    (net (code "98") (name "SEG_A") (class "Default")
      (node (ref "R23") (pin "2") (pinfunction "2_2") (pintype "passive"))
      (node (ref "U1") (pin "83") (pinfunction "IO_83_83") (pintype "bidirectional"))
    )
    (net (code "99") (name "SEG_B") (class "Default")
      (node (ref "R19") (pin "2") (pinfunction "2_2") (pintype "passive"))
      (node (ref "U1") (pin "84") (pinfunction "IO_84_84") (pintype "bidirectional"))
    )
    (net (code "100") (name "SEG_C") (class "Default")
      (node (ref "R24") (pin "2") (pinfunction "2_2") (pintype "passive"))
      (node (ref "U1") (pin "85") (pinfunction "IO_85_85") (pintype "bidirectional"))
    )
    (net (code "101") (name "SEG_D") (class "Default")
      (node (ref "R20") (pin "2") (pinfunction "2_2") (pintype "passive"))
      (node (ref "U1") (pin "86") (pinfunction "IO_86_86") (pintype "bidirectional"))
    )
    (net (code "102") (name "SEG_DP") (class "Default")
      (node (ref "R22") (pin "2") (pinfunction "2_2") (pintype "passive"))
      (node (ref "U1") (pin "90") (pinfunction "IO_90_90") (pintype "bidirectional"))
    )
    (net (code "103") (name "SEG_E") (class "Default")
      (node (ref "R25") (pin "2") (pinfunction "2_2") (pintype "passive"))
      (node (ref "U1") (pin "87") (pinfunction "IO_87_87") (pintype "bidirectional"))
    )
    (net (code "104") (name "SEG_F") (class "Default")
      (node (ref "R21") (pin "2") (pinfunction "2_2") (pintype "passive"))
      (node (ref "U1") (pin "88") (pinfunction "IO_88_88") (pintype "bidirectional"))
    )
    (net (code "105") (name "SEG_G") (class "Default")
      (node (ref "R26") (pin "2") (pinfunction "2_2") (pintype "passive"))
      (node (ref "U1") (pin "89") (pinfunction "IO_89_89") (pintype "bidirectional"))
    )
    (net (code "106") (name "SW_1") (class "Default")
      (node (ref "CER13") (pin "P$2") (pinfunction "P$2_P$2") (pintype "passive"))
      (node (ref "R3") (pin "1") (pinfunction "1_1") (pintype "passive"))
      (node (ref "U1") (pin "91") (pinfunction "IO_91_91") (pintype "bidirectional"))
    )
    (net (code "107") (name "SW_2") (class "Default")
      (node (ref "CER14") (pin "P$2") (pinfunction "P$2_P$2") (pintype "passive"))
      (node (ref "R5") (pin "1") (pinfunction "1_1") (pintype "passive"))
      (node (ref "U1") (pin "92") (pinfunction "IO_92_92") (pintype "bidirectional"))
    )
    (net (code "108") (name "SW_3") (class "Default")
      (node (ref "CER15") (pin "P$2") (pinfunction "P$2_P$2") (pintype "passive"))
      (node (ref "R7") (pin "1") (pinfunction "1_1") (pintype "passive"))
      (node (ref "U1") (pin "95") (pinfunction "IO_95_95") (pintype "bidirectional"))
    )
    (net (code "109") (name "SW_4") (class "Default")
      (node (ref "CER16") (pin "P$2") (pinfunction "P$2_P$2") (pintype "passive"))
      (node (ref "R9") (pin "1") (pinfunction "1_1") (pintype "passive"))
      (node (ref "U1") (pin "96") (pinfunction "IO_96_96") (pintype "bidirectional"))
    )
    (net (code "110") (name "TCK_IC1") (class "Default")
      (node (ref "U1") (pin "24") (pinfunction "TCK_24") (pintype "input"))
      (node (ref "X2") (pin "9") (pinfunction "1_9") (pintype "passive"))
    )
    (net (code "111") (name "TDI_IC1") (class "Default")
      (node (ref "U1") (pin "23") (pinfunction "TDI_23") (pintype "input"))
      (node (ref "X2") (pin "1") (pinfunction "1_1") (pintype "passive"))
    )
    (net (code "112") (name "TDO_IC1") (class "Default")
      (node (ref "U1") (pin "25") (pinfunction "TDO_25") (pintype "output"))
      (node (ref "X2") (pin "7") (pinfunction "1_7") (pintype "passive"))
    )
    (net (code "113") (name "TMS_IC1") (class "Default")
      (node (ref "U1") (pin "22") (pinfunction "TMS_22") (pintype "input"))
      (node (ref "X2") (pin "5") (pinfunction "1_5") (pintype "passive"))
    )
    (net (code "114") (name "unconnected-(J1-D+-Pad3)") (class "Default")
      (node (ref "J1") (pin "3") (pinfunction "D+_3") (pintype "bidirectional"))
    )
    (net (code "115") (name "unconnected-(J1-D--Pad2)") (class "Default")
      (node (ref "J1") (pin "2") (pinfunction "D-_2") (pintype "bidirectional"))
    )
    (net (code "116") (name "unconnected-(SW1-Pad2)") (class "Default")
      (node (ref "SW1") (pin "2") (pinfunction "2_2") (pintype "passive"))
    )
    (net (code "117") (name "unconnected-(SW1-Pad4)") (class "Default")
      (node (ref "SW1") (pin "4") (pinfunction "4_4") (pintype "passive"))
    )
    (net (code "118") (name "unconnected-(SW2-Pad2)") (class "Default")
      (node (ref "SW2") (pin "2") (pinfunction "2_2") (pintype "passive"))
    )
    (net (code "119") (name "unconnected-(SW2-Pad4)") (class "Default")
      (node (ref "SW2") (pin "4") (pinfunction "4_4") (pintype "passive"))
    )
    (net (code "120") (name "unconnected-(SW3-Pad2)") (class "Default")
      (node (ref "SW3") (pin "2") (pinfunction "2_2") (pintype "passive"))
    )
    (net (code "121") (name "unconnected-(SW3-Pad4)") (class "Default")
      (node (ref "SW3") (pin "4") (pinfunction "4_4") (pintype "passive"))
    )
    (net (code "122") (name "unconnected-(SW4-Pad2)") (class "Default")
      (node (ref "SW4") (pin "2") (pinfunction "2_2") (pintype "passive"))
    )
    (net (code "123") (name "unconnected-(SW4-Pad4)") (class "Default")
      (node (ref "SW4") (pin "4") (pinfunction "4_4") (pintype "passive"))
    )
    (net (code "124") (name "unconnected-(SW5-Pad2)") (class "Default")
      (node (ref "SW5") (pin "2") (pinfunction "2_2") (pintype "passive"))
    )
    (net (code "125") (name "unconnected-(SW5-Pad4)") (class "Default")
      (node (ref "SW5") (pin "4") (pinfunction "4_4") (pintype "passive"))
    )
    (net (code "126") (name "unconnected-(X2D-1-Pad3)") (class "Default")
      (node (ref "X2") (pin "3") (pinfunction "1_3") (pintype "passive"))
    )
    (net (code "127") (name "unconnected-(X2E-1-Pad4)") (class "Default")
      (node (ref "X2") (pin "4") (pinfunction "1_4") (pintype "passive"))
    )
    (net (code "128") (name "unconnected-(X2G-1-Pad6)") (class "Default")
      (node (ref "X2") (pin "6") (pinfunction "1_6") (pintype "passive"))
    )
  )
)
